# eeZeeAmpJig.net
KiCad netlist of a schematic drawn in EAGLE
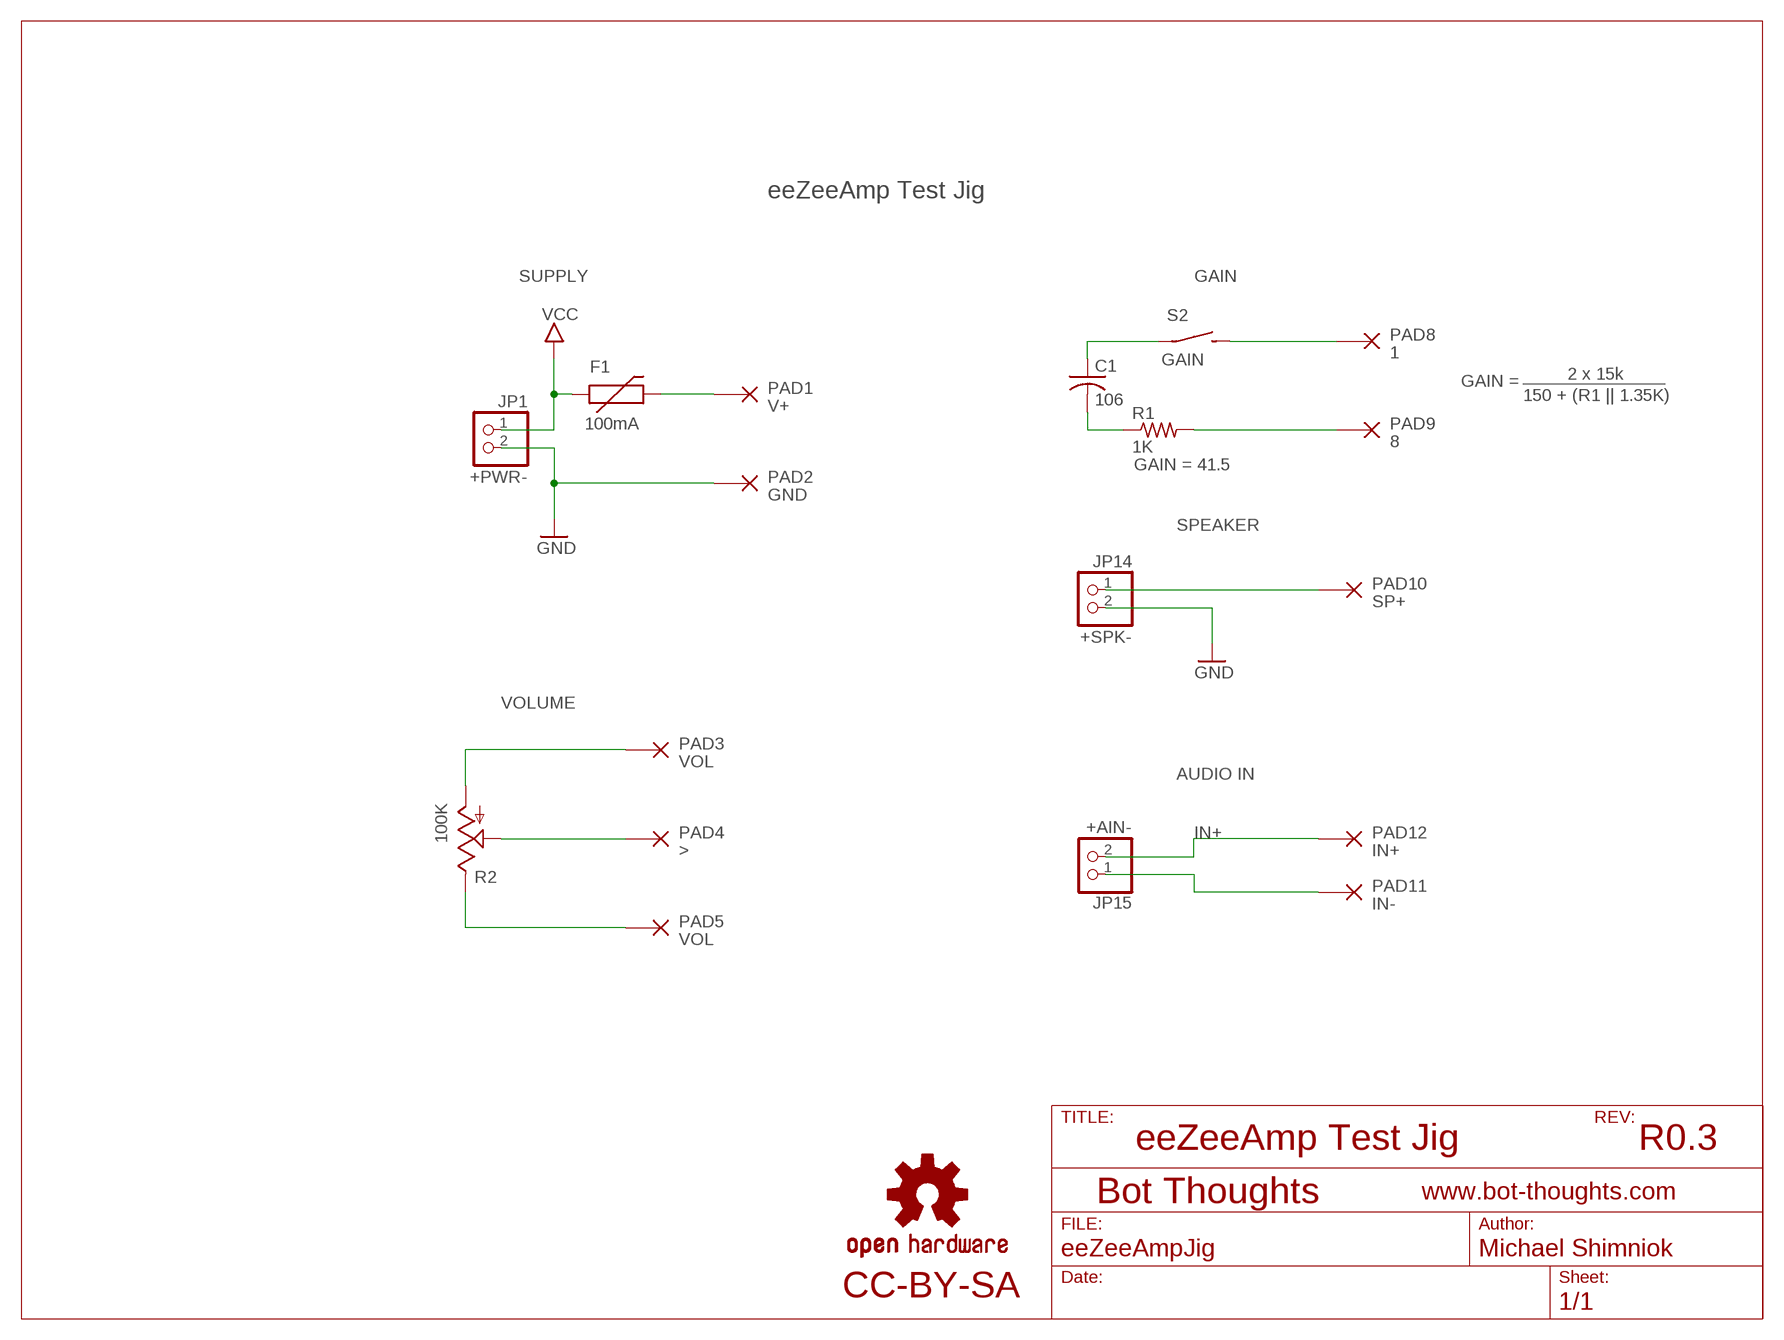
[diagram p0: schematic, sheet 1]

(export (version "E")
  (design (tool "Eeschema 10.0.6"))
  (components
    (comp (ref "C1")
      (value "106")
      (footprint "eagle-import:C0805")
      (libsource (lib "eagle-import") (part "C-USC0805"))
    )
    (comp (ref "F1")
      (value "100mA")
      (footprint "eagle-import:0603")
      (libsource (lib "eagle-import") (part "PTC0603"))
    )
    (comp (ref "JP1")
      (value "+PWR-")
      (footprint "eagle-import:1X02-S")
      (libsource (lib "eagle-import") (part "PINHD-1X02_2.54-S"))
    )
    (comp (ref "JP14")
      (value "+SPK-")
      (footprint "eagle-import:1X02-S")
      (libsource (lib "eagle-import") (part "PINHD-1X02_2.54-S"))
    )
    (comp (ref "JP15")
      (value "+AIN-")
      (footprint "eagle-import:1X02-S")
      (libsource (lib "eagle-import") (part "PINHD-1X02_2.54-S"))
    )
    (comp (ref "LOGO2")
      (value "OSHW-LOGOS")
      (footprint "eagle-import:OSHW-LOGO-S")
      (libsource (lib "eagle-import") (part "OSHW-LOGOS"))
    )
    (comp (ref "PAD1")
      (value "V+")
      (footprint "eagle-import:POGO_1.02MM")
      (libsource (lib "eagle-import") (part "WIREPAD_1.2MM"))
    )
    (comp (ref "PAD2")
      (value "GND")
      (footprint "eagle-import:POGO_1.02MM")
      (libsource (lib "eagle-import") (part "WIREPAD_1.2MM"))
    )
    (comp (ref "PAD3")
      (value "VOL")
      (footprint "eagle-import:POGO_1.02MM")
      (libsource (lib "eagle-import") (part "WIREPAD_1.2MM"))
    )
    (comp (ref "PAD4")
      (value ">")
      (footprint "eagle-import:POGO_1.02MM")
      (libsource (lib "eagle-import") (part "WIREPAD_1.2MM"))
    )
    (comp (ref "PAD5")
      (value "VOL")
      (footprint "eagle-import:POGO_1.02MM")
      (libsource (lib "eagle-import") (part "WIREPAD_1.2MM"))
    )
    (comp (ref "PAD8")
      (value "1")
      (footprint "eagle-import:POGO_1.02MM")
      (libsource (lib "eagle-import") (part "WIREPAD_1.2MM"))
    )
    (comp (ref "PAD9")
      (value "8")
      (footprint "eagle-import:POGO_1.02MM")
      (libsource (lib "eagle-import") (part "WIREPAD_1.2MM"))
    )
    (comp (ref "PAD10")
      (value "SP+")
      (footprint "eagle-import:POGO_1.02MM")
      (libsource (lib "eagle-import") (part "WIREPAD_1.2MM"))
    )
    (comp (ref "PAD11")
      (value "IN-")
      (footprint "eagle-import:POGO_1.02MM")
      (libsource (lib "eagle-import") (part "WIREPAD_1.2MM"))
    )
    (comp (ref "PAD12")
      (value "IN+")
      (footprint "eagle-import:POGO_1.02MM")
      (libsource (lib "eagle-import") (part "WIREPAD_1.2MM"))
    )
    (comp (ref "R1")
      (value "1K")
      (footprint "eagle-import:R0603")
      (libsource (lib "eagle-import") (part "R-US_R0603"))
    )
    (comp (ref "R2")
      (value "100K")
      (footprint "eagle-import:CA6H")
      (libsource (lib "eagle-import") (part "TRIM_US-CA6H"))
    )
    (comp (ref "S2")
      (value "GAIN")
      (footprint "eagle-import:3X4X2TACT")
      (libsource (lib "eagle-import") (part "SPST_3X4X2"))
    )
  )
  (nets
    (net (code "1") (name "/IN+") (class "Default")
      (node (ref "JP15") (pin "2") (pinfunction "2_2") (pintype "passive"))
      (node (ref "PAD12") (pin "P$1") (pinfunction "P_P$1") (pintype "bidirectional"))
    )
    (net (code "2") (name "GND") (class "Default")
      (node (ref "JP1") (pin "2") (pinfunction "2_2") (pintype "passive"))
      (node (ref "JP14") (pin "2") (pinfunction "2_2") (pintype "passive"))
      (node (ref "PAD2") (pin "P$1") (pinfunction "P_P$1") (pintype "bidirectional"))
    )
    (net (code "3") (name "Net-(C1-Pad2)") (class "Default")
      (node (ref "C1") (pin "2") (pinfunction "2_2") (pintype "passive"))
      (node (ref "R1") (pin "1") (pinfunction "1_1") (pintype "passive"))
    )
    (net (code "4") (name "Net-(PAD1-P)") (class "Default")
      (node (ref "F1") (pin "2") (pinfunction "2_2") (pintype "bidirectional"))
      (node (ref "PAD1") (pin "P$1") (pinfunction "P_P$1") (pintype "bidirectional"))
    )
    (net (code "5") (name "Net-(PAD3-P)") (class "Default")
      (node (ref "PAD3") (pin "P$1") (pinfunction "P_P$1") (pintype "bidirectional"))
      (node (ref "R2") (pin "A") (pinfunction "A_A") (pintype "passive"))
    )
    (net (code "6") (name "Net-(PAD4-P)") (class "Default")
      (node (ref "PAD4") (pin "P$1") (pinfunction "P_P$1") (pintype "bidirectional"))
      (node (ref "R2") (pin "S") (pinfunction "S_S") (pintype "passive"))
    )
    (net (code "7") (name "Net-(PAD5-P)") (class "Default")
      (node (ref "PAD5") (pin "P$1") (pinfunction "P_P$1") (pintype "bidirectional"))
      (node (ref "R2") (pin "E") (pinfunction "E_E") (pintype "passive"))
    )
    (net (code "8") (name "Net-(PAD8-P)") (class "Default")
      (node (ref "PAD8") (pin "P$1") (pinfunction "P_P$1") (pintype "bidirectional"))
      (node (ref "S2") (pin "P$2") (pinfunction "S_P$2") (pintype "passive"))
    )
    (net (code "9") (name "Net-(PAD9-P)") (class "Default")
      (node (ref "PAD9") (pin "P$1") (pinfunction "P_P$1") (pintype "bidirectional"))
      (node (ref "R1") (pin "2") (pinfunction "2_2") (pintype "passive"))
    )
    (net (code "10") (name "Net-(PAD10-P)") (class "Default")
      (node (ref "JP14") (pin "1") (pinfunction "1_1") (pintype "passive"))
      (node (ref "PAD10") (pin "P$1") (pinfunction "P_P$1") (pintype "bidirectional"))
    )
    (net (code "11") (name "Net-(PAD11-P)") (class "Default")
      (node (ref "JP15") (pin "1") (pinfunction "1_1") (pintype "passive"))
      (node (ref "PAD11") (pin "P$1") (pinfunction "P_P$1") (pintype "bidirectional"))
    )
    (net (code "12") (name "Net-(S2-P)") (class "Default")
      (node (ref "C1") (pin "1") (pinfunction "1_1") (pintype "passive"))
      (node (ref "S2") (pin "P$1") (pinfunction "P_P$1") (pintype "passive"))
    )
    (net (code "13") (name "VCC") (class "Default")
      (node (ref "F1") (pin "1") (pinfunction "1_1") (pintype "bidirectional"))
      (node (ref "JP1") (pin "1") (pinfunction "1_1") (pintype "passive"))
    )
  )
)
